# Solder_Reflow_Oven_Shield.net
KiCad netlist of a schematic drawn in EAGLE
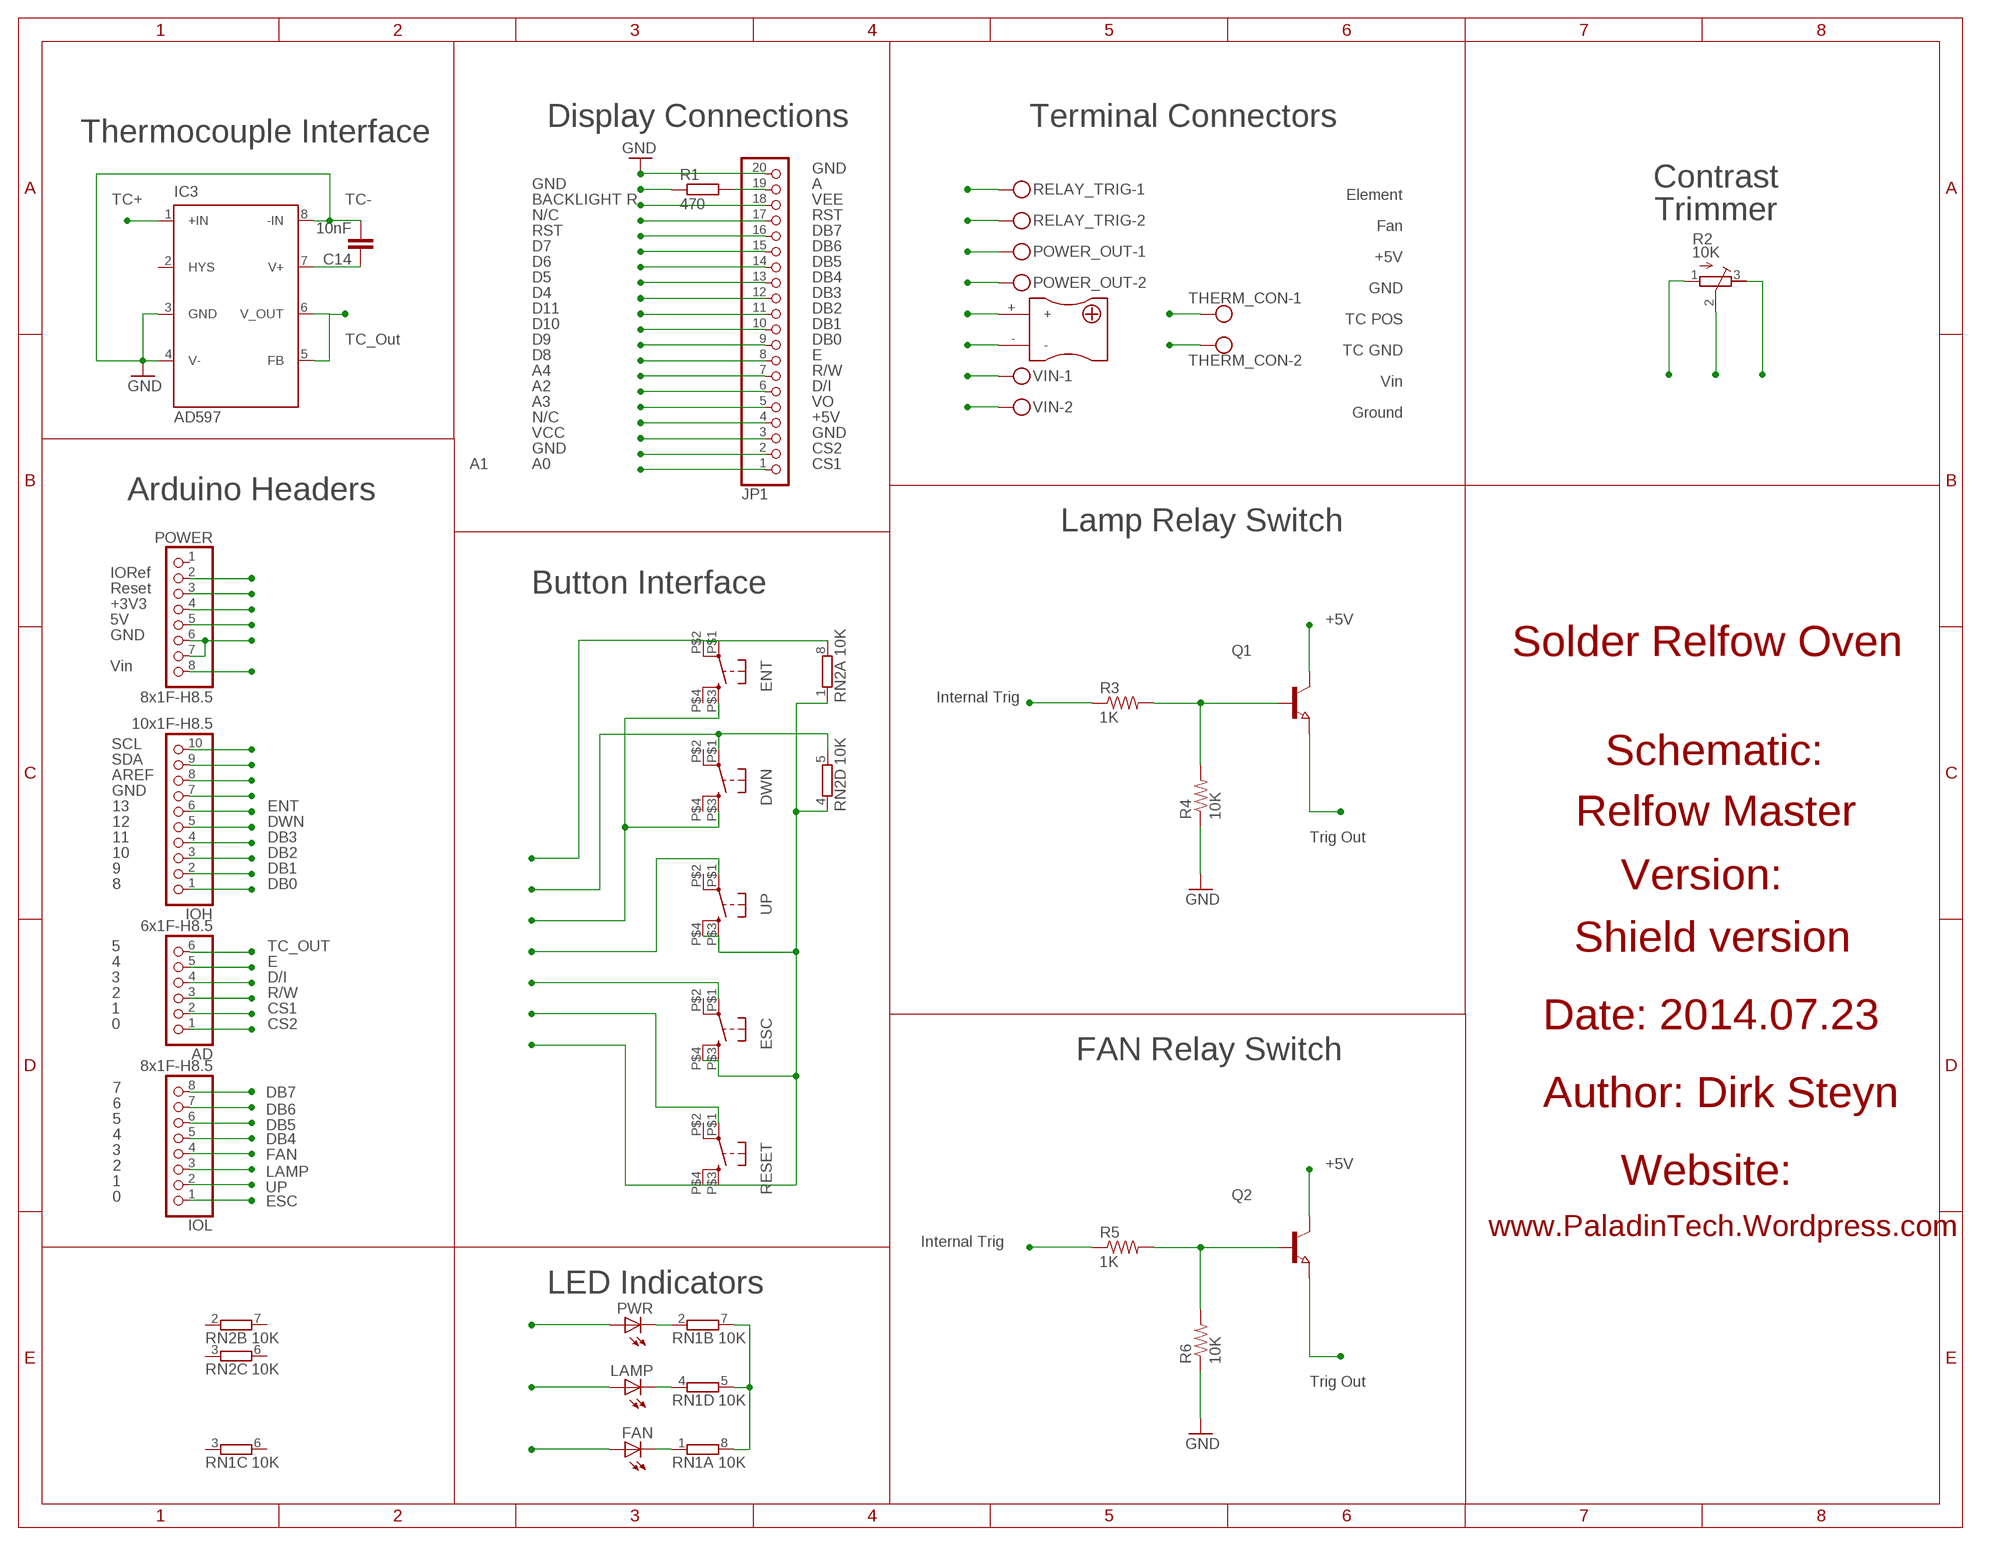
[diagram p0: schematic, sheet 1]

(export (version "E")
  (design (tool "Eeschema 10.0.6"))
  (components
    (comp (ref "AD")
      (value "6x1F-H8.5")
      (footprint "eagle-import:1X06")
      (libsource (lib "eagle-import") (part "PINHD-1X6"))
    )
    (comp (ref "C14")
      (value "10nF")
      (footprint "eagle-import:C0603")
      (libsource (lib "eagle-import") (part "C-EUC0603"))
    )
    (comp (ref "DWN")
      (value "MANTECH_TAC")
      (footprint "eagle-import:MANTECH_TAC")
      (libsource (lib "eagle-import") (part "MANTECH_TAC"))
    )
    (comp (ref "ENT")
      (value "MANTECH_TAC")
      (footprint "eagle-import:MANTECH_TAC")
      (libsource (lib "eagle-import") (part "MANTECH_TAC"))
    )
    (comp (ref "ESC")
      (value "MANTECH_TAC")
      (footprint "eagle-import:MANTECH_TAC")
      (libsource (lib "eagle-import") (part "MANTECH_TAC"))
    )
    (comp (ref "FAN")
      (value "LEDCHIP-LED0603")
      (footprint "eagle-import:CHIP-LED0603")
      (libsource (lib "eagle-import") (part "LEDCHIP-LED0603"))
    )
    (comp (ref "IC3")
      (value "AD597")
      (footprint "eagle-import:SO8")
      (libsource (lib "eagle-import") (part "AD597"))
    )
    (comp (ref "IOH")
      (value "10x1F-H8.5")
      (footprint "eagle-import:1X10")
      (libsource (lib "eagle-import") (part "PINHD-1X10_ARD"))
    )
    (comp (ref "IOL")
      (value "8x1F-H8.5")
      (footprint "eagle-import:1X08")
      (libsource (lib "eagle-import") (part "PINHD-1X8"))
    )
    (comp (ref "JP1")
      (value "PINHD-1X20")
      (footprint "eagle-import:1X20")
      (libsource (lib "eagle-import") (part "PINHD-1X20"))
    )
    (comp (ref "LAMP")
      (value "LEDCHIP-LED0603")
      (footprint "eagle-import:CHIP-LED0603")
      (libsource (lib "eagle-import") (part "LEDCHIP-LED0603"))
    )
    (comp (ref "POWER")
      (value "8x1F-H8.5")
      (footprint "eagle-import:1X08")
      (libsource (lib "eagle-import") (part "PINHD-1X8"))
    )
    (comp (ref "POWER_OUT")
      (value "MKDSN1,5/2-5,08")
      (footprint "eagle-import:2XPCB_TER")
      (libsource (lib "eagle-import") (part "MKDSN1,5/2-5,08"))
    )
    (comp (ref "PWR")
      (value "LEDCHIP-LED0603")
      (footprint "eagle-import:CHIP-LED0603")
      (libsource (lib "eagle-import") (part "LEDCHIP-LED0603"))
    )
    (comp (ref "Q1")
      (value "NPN-TRANSISTOR_SOT23")
      (footprint "eagle-import:SOT23")
      (libsource (lib "eagle-import") (part "NPN-TRANSISTOR_SOT23"))
    )
    (comp (ref "Q2")
      (value "NPN-TRANSISTOR_SOT23")
      (footprint "eagle-import:SOT23")
      (libsource (lib "eagle-import") (part "NPN-TRANSISTOR_SOT23"))
    )
    (comp (ref "R1")
      (value "470")
      (footprint "eagle-import:R0603")
      (libsource (lib "eagle-import") (part "R-EU_R0603"))
    )
    (comp (ref "R2")
      (value "10K")
      (footprint "eagle-import:MURATA_PVZ3A")
      (libsource (lib "eagle-import") (part "MURATA_PVZ3A"))
    )
    (comp (ref "R3")
      (value "1K")
      (footprint "eagle-import:R0603")
      (libsource (lib "eagle-import") (part "R-US_R0603"))
    )
    (comp (ref "R4")
      (value "10K")
      (footprint "eagle-import:R0603")
      (libsource (lib "eagle-import") (part "R-US_R0603"))
    )
    (comp (ref "R5")
      (value "1K")
      (footprint "eagle-import:R0603")
      (libsource (lib "eagle-import") (part "R-US_R0603"))
    )
    (comp (ref "R6")
      (value "10K")
      (footprint "eagle-import:R0603")
      (libsource (lib "eagle-import") (part "R-US_R0603"))
    )
    (comp (ref "RELAY_TRIG")
      (value "MKDSN1,5/2-5,08")
      (footprint "eagle-import:2XPCB_TER")
      (libsource (lib "eagle-import") (part "MKDSN1,5/2-5,08"))
    )
    (comp (ref "RESET")
      (value "MANTECH_TAC")
      (footprint "eagle-import:MANTECH_TAC")
      (libsource (lib "eagle-import") (part "MANTECH_TAC"))
    )
    (comp (ref "RN1")
      (value "10K")
      (footprint "eagle-import:EXB38V")
      (libsource (lib "eagle-import") (part "4R-NEXB38V"))
    )
    (comp (ref "RN2")
      (value "10K")
      (footprint "eagle-import:EXB38V")
      (libsource (lib "eagle-import") (part "4R-NEXB38V"))
    )
    (comp (ref "THERM_CON")
      (value "MKDSN1,5/2-5,08")
      (footprint "eagle-import:2XPCB_TER")
      (libsource (lib "eagle-import") (part "MKDSN1,5/2-5,08"))
    )
    (comp (ref "U$1")
      (value "THERMOCOUPLEPLUG_MINI")
      (footprint "eagle-import:TC-MINI")
      (libsource (lib "eagle-import") (part "THERMOCOUPLEPLUG_MINI"))
    )
    (comp (ref "UP")
      (value "MANTECH_TAC")
      (footprint "eagle-import:MANTECH_TAC")
      (libsource (lib "eagle-import") (part "MANTECH_TAC"))
    )
    (comp (ref "VIN")
      (value "MKDSN1,5/2-5,08")
      (footprint "eagle-import:2XPCB_TER")
      (libsource (lib "eagle-import") (part "MKDSN1,5/2-5,08"))
    )
  )
  (nets
    (net (code "1") (name "/+5V") (class "Default")
      (node (ref "C14") (pin "1") (pinfunction "1_1") (pintype "passive"))
      (node (ref "DWN") (pin "P$3") (pinfunction "3_P$3") (pintype "passive"))
      (node (ref "ENT") (pin "P$3") (pinfunction "3_P$3") (pintype "passive"))
      (node (ref "IC3") (pin "7") (pinfunction "V+_7") (pintype "passive"))
      (node (ref "JP1") (pin "4") (pinfunction "4_4") (pintype "passive"))
      (node (ref "POWER") (pin "5") (pinfunction "5_5") (pintype "passive"))
      (node (ref "POWER_OUT") (pin "1") (pinfunction "KL_1") (pintype "passive"))
      (node (ref "PWR") (pin "A") (pinfunction "A_A") (pintype "passive"))
      (node (ref "Q1") (pin "3") (pinfunction "C_3") (pintype "passive"))
      (node (ref "Q2") (pin "3") (pinfunction "C_3") (pintype "passive"))
      (node (ref "R1") (pin "1") (pinfunction "1_1") (pintype "passive"))
    )
    (net (code "2") (name "/CS1") (class "Default")
      (node (ref "AD") (pin "2") (pinfunction "2_2") (pintype "passive"))
      (node (ref "JP1") (pin "1") (pinfunction "1_1") (pintype "passive"))
    )
    (net (code "3") (name "/CS2") (class "Default")
      (node (ref "AD") (pin "1") (pinfunction "1_1") (pintype "passive"))
      (node (ref "JP1") (pin "2") (pinfunction "2_2") (pintype "passive"))
    )
    (net (code "4") (name "/DB0") (class "Default")
      (node (ref "IOH") (pin "1") (pinfunction "1_1") (pintype "passive"))
      (node (ref "JP1") (pin "9") (pinfunction "9_9") (pintype "passive"))
    )
    (net (code "5") (name "/DB1") (class "Default")
      (node (ref "IOH") (pin "2") (pinfunction "2_2") (pintype "passive"))
      (node (ref "JP1") (pin "10") (pinfunction "10_10") (pintype "passive"))
    )
    (net (code "6") (name "/DB2") (class "Default")
      (node (ref "IOH") (pin "3") (pinfunction "3_3") (pintype "passive"))
      (node (ref "JP1") (pin "11") (pinfunction "11_11") (pintype "passive"))
    )
    (net (code "7") (name "/DB3") (class "Default")
      (node (ref "IOH") (pin "4") (pinfunction "4_4") (pintype "passive"))
      (node (ref "JP1") (pin "12") (pinfunction "12_12") (pintype "passive"))
    )
    (net (code "8") (name "/DB4") (class "Default")
      (node (ref "IOL") (pin "5") (pinfunction "5_5") (pintype "passive"))
      (node (ref "JP1") (pin "13") (pinfunction "13_13") (pintype "passive"))
    )
    (net (code "9") (name "/DB5") (class "Default")
      (node (ref "IOL") (pin "6") (pinfunction "6_6") (pintype "passive"))
      (node (ref "JP1") (pin "14") (pinfunction "14_14") (pintype "passive"))
    )
    (net (code "10") (name "/DB6") (class "Default")
      (node (ref "IOL") (pin "7") (pinfunction "7_7") (pintype "passive"))
      (node (ref "JP1") (pin "15") (pinfunction "15_15") (pintype "passive"))
    )
    (net (code "11") (name "/DB7") (class "Default")
      (node (ref "IOL") (pin "8") (pinfunction "8_8") (pintype "passive"))
      (node (ref "JP1") (pin "16") (pinfunction "16_16") (pintype "passive"))
    )
    (net (code "12") (name "/DWN") (class "Default")
      (node (ref "DWN") (pin "P$1") (pinfunction "1_P$1") (pintype "passive"))
      (node (ref "IOH") (pin "5") (pinfunction "5_5") (pintype "passive"))
      (node (ref "RN2") (pin "5") (pinfunction "2_5") (pintype "passive"))
    )
    (net (code "13") (name "/D{slash}I") (class "Default")
      (node (ref "AD") (pin "4") (pinfunction "4_4") (pintype "passive"))
      (node (ref "JP1") (pin "6") (pinfunction "6_6") (pintype "passive"))
    )
    (net (code "14") (name "/E") (class "Default")
      (node (ref "AD") (pin "5") (pinfunction "5_5") (pintype "passive"))
      (node (ref "JP1") (pin "8") (pinfunction "8_8") (pintype "passive"))
    )
    (net (code "15") (name "/ELEMENT_OUT") (class "Default")
      (node (ref "Q1") (pin "2") (pinfunction "E_2") (pintype "passive"))
      (node (ref "RELAY_TRIG") (pin "1") (pinfunction "KL_1") (pintype "passive"))
    )
    (net (code "16") (name "/ENT") (class "Default")
      (node (ref "ENT") (pin "P$1") (pinfunction "1_P$1") (pintype "passive"))
      (node (ref "ENT") (pin "P$2") (pinfunction "2_P$2") (pintype "passive"))
      (node (ref "IOH") (pin "6") (pinfunction "6_6") (pintype "passive"))
      (node (ref "RN2") (pin "8") (pinfunction "2_8") (pintype "passive"))
    )
    (net (code "17") (name "/ESC") (class "Default")
      (node (ref "ESC") (pin "P$1") (pinfunction "1_P$1") (pintype "passive"))
      (node (ref "IOL") (pin "1") (pinfunction "1_1") (pintype "passive"))
    )
    (net (code "18") (name "/FAN") (class "Default")
      (node (ref "FAN") (pin "A") (pinfunction "A_A") (pintype "passive"))
      (node (ref "IOL") (pin "4") (pinfunction "4_4") (pintype "passive"))
      (node (ref "R5") (pin "1") (pinfunction "1_1") (pintype "passive"))
    )
    (net (code "19") (name "/FAN_OUT") (class "Default")
      (node (ref "Q2") (pin "2") (pinfunction "E_2") (pintype "passive"))
      (node (ref "RELAY_TRIG") (pin "2") (pinfunction "KL_2") (pintype "passive"))
    )
    (net (code "20") (name "/LAMP") (class "Default")
      (node (ref "IOL") (pin "3") (pinfunction "3_3") (pintype "passive"))
      (node (ref "LAMP") (pin "A") (pinfunction "A_A") (pintype "passive"))
      (node (ref "R3") (pin "1") (pinfunction "1_1") (pintype "passive"))
    )
    (net (code "21") (name "/RST") (class "Default")
      (node (ref "JP1") (pin "17") (pinfunction "17_17") (pintype "passive"))
      (node (ref "POWER") (pin "3") (pinfunction "3_3") (pintype "passive"))
      (node (ref "RESET") (pin "P$1") (pinfunction "1_P$1") (pintype "passive"))
    )
    (net (code "22") (name "/R{slash}W") (class "Default")
      (node (ref "AD") (pin "3") (pinfunction "3_3") (pintype "passive"))
      (node (ref "JP1") (pin "7") (pinfunction "7_7") (pintype "passive"))
    )
    (net (code "23") (name "/TC+") (class "Default")
      (node (ref "IC3") (pin "1") (pinfunction "+IN_1") (pintype "input"))
      (node (ref "THERM_CON") (pin "1") (pinfunction "KL_1") (pintype "passive"))
      (node (ref "U$1") (pin "+") (pinfunction "+_+") (pintype "bidirectional"))
    )
    (net (code "24") (name "/TC_OUT") (class "Default")
      (node (ref "AD") (pin "6") (pinfunction "6_6") (pintype "passive"))
      (node (ref "IC3") (pin "5") (pinfunction "FB_5") (pintype "power_in"))
      (node (ref "IC3") (pin "6") (pinfunction "V_OUT_6") (pintype "passive"))
    )
    (net (code "25") (name "/UP") (class "Default")
      (node (ref "IOL") (pin "2") (pinfunction "2_2") (pintype "passive"))
      (node (ref "UP") (pin "P$1") (pinfunction "1_P$1") (pintype "passive"))
    )
    (net (code "26") (name "/VEE") (class "Default")
      (node (ref "JP1") (pin "18") (pinfunction "18_18") (pintype "passive"))
      (node (ref "R2") (pin "1") (pinfunction "1_1") (pintype "passive"))
    )
    (net (code "27") (name "/VIN") (class "Default")
      (node (ref "POWER") (pin "8") (pinfunction "8_8") (pintype "passive"))
      (node (ref "VIN") (pin "1") (pinfunction "KL_1") (pintype "passive"))
    )
    (net (code "28") (name "/VO") (class "Default")
      (node (ref "JP1") (pin "5") (pinfunction "5_5") (pintype "passive"))
      (node (ref "R2") (pin "2") (pinfunction "2_2") (pintype "passive"))
    )
    (net (code "29") (name "GND") (class "Default")
      (node (ref "C14") (pin "2") (pinfunction "2_2") (pintype "passive"))
      (node (ref "ESC") (pin "P$3") (pinfunction "3_P$3") (pintype "passive"))
      (node (ref "ESC") (pin "P$4") (pinfunction "4_P$4") (pintype "passive"))
      (node (ref "IC3") (pin "3") (pinfunction "GND_3") (pintype "passive"))
      (node (ref "IC3") (pin "4") (pinfunction "V-_4") (pintype "passive"))
      (node (ref "IC3") (pin "8") (pinfunction "-IN_8") (pintype "power_in"))
      (node (ref "IOH") (pin "7") (pinfunction "7_7") (pintype "passive"))
      (node (ref "JP1") (pin "20") (pinfunction "20_20") (pintype "passive"))
      (node (ref "JP1") (pin "3") (pinfunction "3_3") (pintype "passive"))
      (node (ref "POWER") (pin "6") (pinfunction "6_6") (pintype "passive"))
      (node (ref "POWER") (pin "7") (pinfunction "7_7") (pintype "passive"))
      (node (ref "POWER_OUT") (pin "2") (pinfunction "KL_2") (pintype "passive"))
      (node (ref "R2") (pin "3") (pinfunction "3_3") (pintype "passive"))
      (node (ref "R4") (pin "1") (pinfunction "1_1") (pintype "passive"))
      (node (ref "R6") (pin "1") (pinfunction "1_1") (pintype "passive"))
      (node (ref "RESET") (pin "P$3") (pinfunction "3_P$3") (pintype "passive"))
      (node (ref "RESET") (pin "P$4") (pinfunction "4_P$4") (pintype "passive"))
      (node (ref "RN1") (pin "5") (pinfunction "2_5") (pintype "passive"))
      (node (ref "RN1") (pin "7") (pinfunction "2_7") (pintype "passive"))
      (node (ref "RN1") (pin "8") (pinfunction "2_8") (pintype "passive"))
      (node (ref "RN2") (pin "1") (pinfunction "1_1") (pintype "passive"))
      (node (ref "RN2") (pin "4") (pinfunction "1_4") (pintype "passive"))
      (node (ref "THERM_CON") (pin "2") (pinfunction "KL_2") (pintype "passive"))
      (node (ref "U$1") (pin "-") (pinfunction "-_-") (pintype "bidirectional"))
      (node (ref "UP") (pin "P$3") (pinfunction "3_P$3") (pintype "passive"))
      (node (ref "UP") (pin "P$4") (pinfunction "4_P$4") (pintype "passive"))
      (node (ref "VIN") (pin "2") (pinfunction "KL_2") (pintype "passive"))
    )
    (net (code "30") (name "Net-(FAN-PadC)") (class "Default")
      (node (ref "FAN") (pin "C") (pinfunction "C_C") (pintype "passive"))
      (node (ref "RN1") (pin "1") (pinfunction "1_1") (pintype "passive"))
    )
    (net (code "31") (name "Net-(JP1-Pad19)") (class "Default")
      (node (ref "JP1") (pin "19") (pinfunction "19_19") (pintype "passive"))
      (node (ref "R1") (pin "2") (pinfunction "2_2") (pintype "passive"))
    )
    (net (code "32") (name "Net-(Q1-B)") (class "Default")
      (node (ref "Q1") (pin "1") (pinfunction "B_1") (pintype "passive"))
      (node (ref "R3") (pin "2") (pinfunction "2_2") (pintype "passive"))
      (node (ref "R4") (pin "2") (pinfunction "2_2") (pintype "passive"))
    )
    (net (code "33") (name "Net-(Q2-B)") (class "Default")
      (node (ref "Q2") (pin "1") (pinfunction "B_1") (pintype "passive"))
      (node (ref "R5") (pin "2") (pinfunction "2_2") (pintype "passive"))
      (node (ref "R6") (pin "2") (pinfunction "2_2") (pintype "passive"))
    )
    (net (code "34") (name "Net-(RN1B-1)") (class "Default")
      (node (ref "PWR") (pin "C") (pinfunction "C_C") (pintype "passive"))
      (node (ref "RN1") (pin "2") (pinfunction "1_2") (pintype "passive"))
    )
    (net (code "35") (name "Net-(RN1D-1)") (class "Default")
      (node (ref "LAMP") (pin "C") (pinfunction "C_C") (pintype "passive"))
      (node (ref "RN1") (pin "4") (pinfunction "1_4") (pintype "passive"))
    )
    (net (code "36") (name "unconnected-(DWN-2-PadP$2)") (class "Default")
      (node (ref "DWN") (pin "P$2") (pinfunction "2_P$2") (pintype "passive"))
    )
    (net (code "37") (name "unconnected-(DWN-4-PadP$4)") (class "Default")
      (node (ref "DWN") (pin "P$4") (pinfunction "4_P$4") (pintype "passive"))
    )
    (net (code "38") (name "unconnected-(ENT-4-PadP$4)") (class "Default")
      (node (ref "ENT") (pin "P$4") (pinfunction "4_P$4") (pintype "passive"))
    )
    (net (code "39") (name "unconnected-(ESC-2-PadP$2)") (class "Default")
      (node (ref "ESC") (pin "P$2") (pinfunction "2_P$2") (pintype "passive"))
    )
    (net (code "40") (name "unconnected-(IC3-HYS-Pad2)") (class "Default")
      (node (ref "IC3") (pin "2") (pinfunction "HYS_2") (pintype "input"))
    )
    (net (code "41") (name "unconnected-(IOH-Pad8)") (class "Default")
      (node (ref "IOH") (pin "8") (pinfunction "8_8") (pintype "passive"))
    )
    (net (code "42") (name "unconnected-(IOH-Pad9)") (class "Default")
      (node (ref "IOH") (pin "9") (pinfunction "9_9") (pintype "passive"))
    )
    (net (code "43") (name "unconnected-(IOH-Pad10)") (class "Default")
      (node (ref "IOH") (pin "10") (pinfunction "10_10") (pintype "passive"))
    )
    (net (code "44") (name "unconnected-(POWER-Pad1)") (class "Default")
      (node (ref "POWER") (pin "1") (pinfunction "1_1") (pintype "passive"))
    )
    (net (code "45") (name "unconnected-(POWER-Pad2)") (class "Default")
      (node (ref "POWER") (pin "2") (pinfunction "2_2") (pintype "passive"))
    )
    (net (code "46") (name "unconnected-(POWER-Pad4)") (class "Default")
      (node (ref "POWER") (pin "4") (pinfunction "4_4") (pintype "passive"))
    )
    (net (code "47") (name "unconnected-(RESET-2-PadP$2)") (class "Default")
      (node (ref "RESET") (pin "P$2") (pinfunction "2_P$2") (pintype "passive"))
    )
    (net (code "48") (name "unconnected-(RN1C-1-Pad3)") (class "Default")
      (node (ref "RN1") (pin "3") (pinfunction "1_3") (pintype "passive"))
    )
    (net (code "49") (name "unconnected-(RN1C-2-Pad6)") (class "Default")
      (node (ref "RN1") (pin "6") (pinfunction "2_6") (pintype "passive"))
    )
    (net (code "50") (name "unconnected-(RN2B-1-Pad2)") (class "Default")
      (node (ref "RN2") (pin "2") (pinfunction "1_2") (pintype "passive"))
    )
    (net (code "51") (name "unconnected-(RN2B-2-Pad7)") (class "Default")
      (node (ref "RN2") (pin "7") (pinfunction "2_7") (pintype "passive"))
    )
    (net (code "52") (name "unconnected-(RN2C-1-Pad3)") (class "Default")
      (node (ref "RN2") (pin "3") (pinfunction "1_3") (pintype "passive"))
    )
    (net (code "53") (name "unconnected-(RN2C-2-Pad6)") (class "Default")
      (node (ref "RN2") (pin "6") (pinfunction "2_6") (pintype "passive"))
    )
    (net (code "54") (name "unconnected-(UP-2-PadP$2)") (class "Default")
      (node (ref "UP") (pin "P$2") (pinfunction "2_P$2") (pintype "passive"))
    )
  )
)
